# Green_Loop.net
KiCad netlist of a schematic drawn in Altium Designer
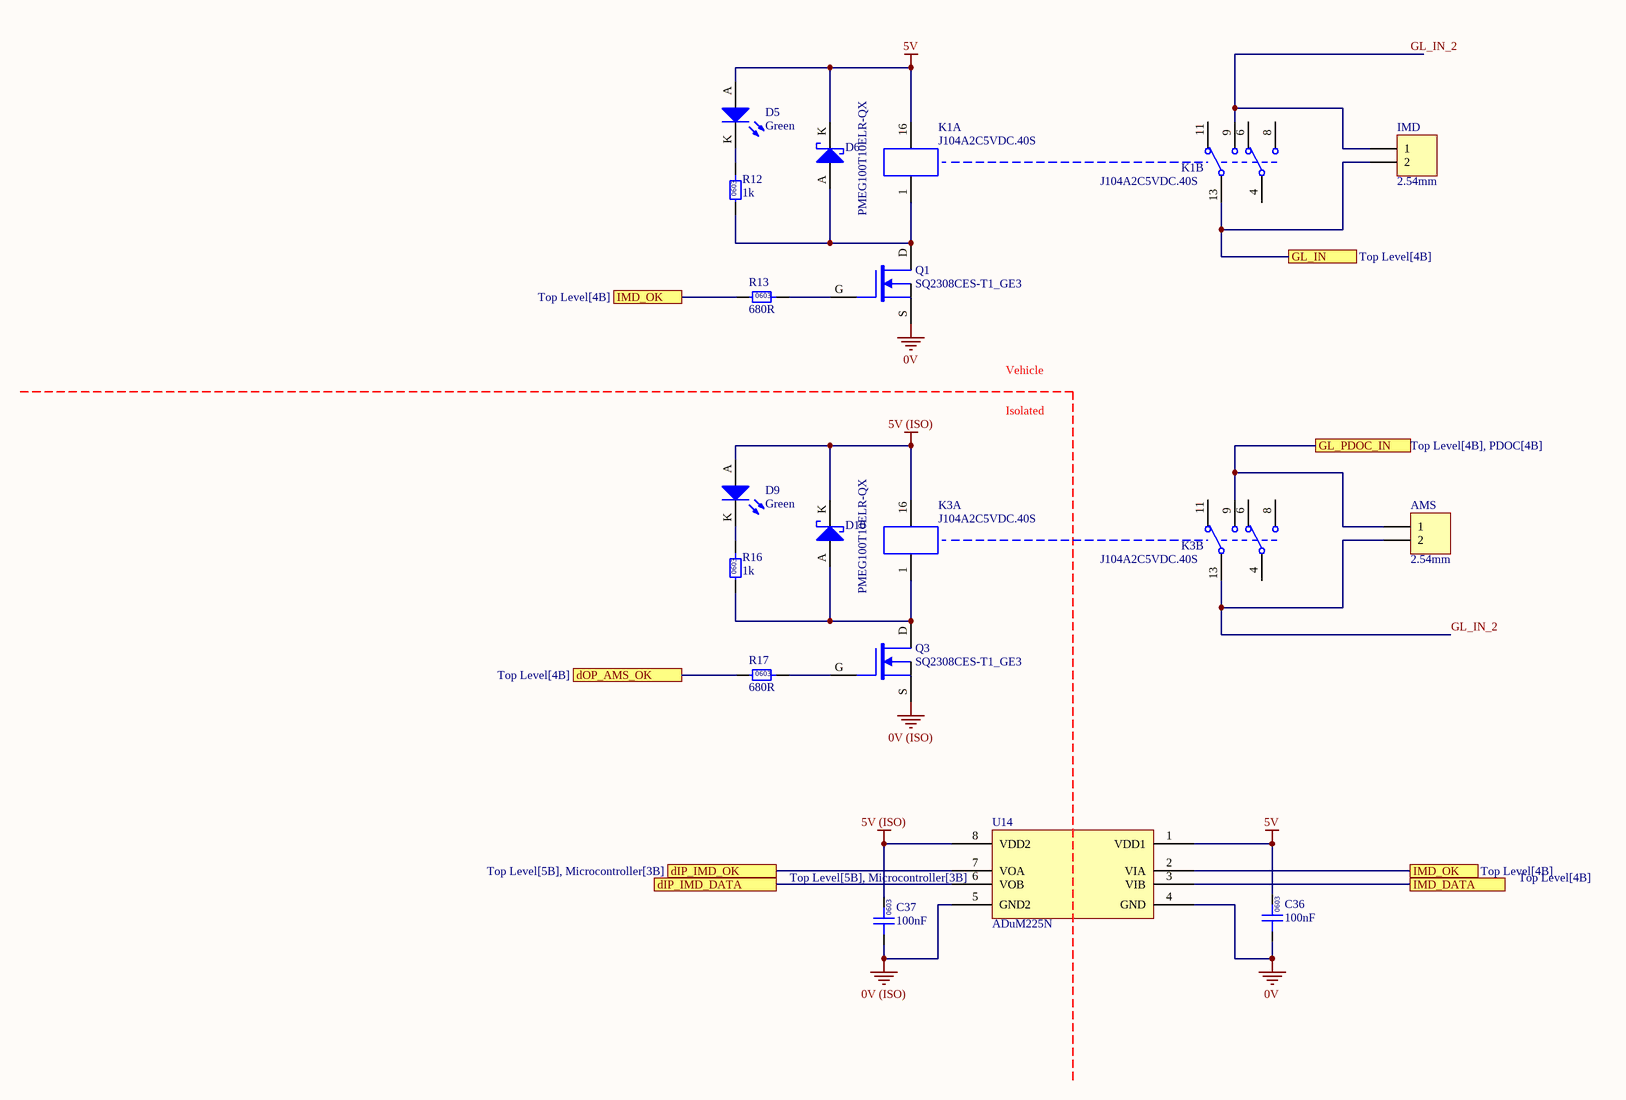
[diagram p0: Green Loop.SchDoc]

(export (version "E")
  (design (tool "Eeschema 10.0.6"))
  (components
    (comp (ref "AMS")
      (value "2.54mm")
      (footprint "TH 2.54mm Header 1x2")
      (fields (field (name "PART NUMBER") "TH 2.54mm Header 1x2") (field (name "CONTACT") "NA"))
      (libsource (lib "ts_standard_connectors") (part "Header 1x2"))
    )
    (comp (ref "C36")
      (value "100nF")
      (footprint "0603")
      (fields
        (field (name "PART NUMBER") "GCM188L81H104KA57D")
        (field (name "MANUFACTURER") "muRata")
        (field (name "TOLERANCE") "±10%")
      )
      (libsource (lib "ts_standard_library") (part "Capacitor 0603"))
    )
    (comp (ref "C37")
      (value "100nF")
      (footprint "0603")
      (fields
        (field (name "PART NUMBER") "GCM188L81H104KA57D")
        (field (name "MANUFACTURER") "muRata")
        (field (name "TOLERANCE") "±10%")
      )
      (libsource (lib "ts_standard_library") (part "Capacitor 0603"))
    )
    (comp (ref "D5")
      (value "Green")
      (footprint "0805 LED")
      (description "Green LED Indication - Discrete 1.75V 0805 (2012 Metric)")
      (fields (field (name "PART NUMBER") "SML-210FTT86") (field (name "MANUFACTURER") "ROHM Semiconductor"))
      (libsource (lib "ts_20-standard-library") (part "LED"))
    )
    (comp (ref "D6")
      (value "PMEG100T10ELR-QX")
      (footprint "NXP SOD123W")
      (fields
        (field (name "MANUFACTURER") "Nexperia USA Inc.")
        (field (name "DIGIKEY PART NUMBER") "1727-PMEG100T10ELR-QXCT-ND")
      )
      (libsource (lib "ts_standard_library") (part "Diode (Schottky)"))
    )
    (comp (ref "D9")
      (value "Green")
      (footprint "0805 LED")
      (description "Green LED Indication - Discrete 1.75V 0805 (2012 Metric)")
      (fields (field (name "PART NUMBER") "SML-210FTT86") (field (name "MANUFACTURER") "ROHM Semiconductor"))
      (libsource (lib "ts_20-standard-library") (part "LED"))
    )
    (comp (ref "D10")
      (value "PMEG100T10ELR-QX")
      (footprint "NXP SOD123W")
      (fields
        (field (name "MANUFACTURER") "Nexperia USA Inc.")
        (field (name "DIGIKEY PART NUMBER") "1727-PMEG100T10ELR-QXCT-ND")
      )
      (libsource (lib "ts_standard_library") (part "Diode (Schottky)"))
    )
    (comp (ref "IMD")
      (value "2.54mm")
      (footprint "TH 2.54mm Header 1x2")
      (fields (field (name "PART NUMBER") "TH 2.54mm Header 1x2") (field (name "CONTACT") "NA"))
      (libsource (lib "ts_standard_connectors") (part "Header 1x2"))
    )
    (comp (ref "K1")
      (value "J104A2C5VDC.40S")
      (footprint "TI 2-DIL")
      (description "RELAY GEN PURPOSE DPDT 3A 5V")
      (fields
        (field (name "MANUFACTURER") "CIT Relay and Switch")
        (field (name "DIGIKEY PART NUMBER") "2449-J104A2C5VDC.40S-ND")
      )
      (libsource (lib "") (part "J104A2C5VDC.40S_1"))
    )
    (comp (ref "K3")
      (value "J104A2C5VDC.40S")
      (footprint "TI 2-DIL")
      (description "RELAY GEN PURPOSE DPDT 3A 5V")
      (fields
        (field (name "MANUFACTURER") "CIT Relay and Switch")
        (field (name "DIGIKEY PART NUMBER") "2449-J104A2C5VDC.40S-ND")
      )
      (libsource (lib "ts_standard_library") (part "J104A2C5VDC.40S"))
    )
    (comp (ref "Q1")
      (value "SQ2308CES-T1_GE3")
      (footprint "VSHY SOT-23-3")
      (description "MOSFET N-CH 60V 2.3A SOT23")
      (fields
        (field (name "MANUFACTURER") "Vishay Siliconix")
        (field (name "DIGIKEY PART NUMBER") "SQ2308CES-T1_GE3CT-ND")
        (field (name "PUBLISHER") "Altium Limited")
      )
      (libsource (lib "ts_standard_library") (part "MOSFET-N"))
    )
    (comp (ref "Q3")
      (value "SQ2308CES-T1_GE3")
      (footprint "VSHY SOT-23-3")
      (description "MOSFET N-CH 60V 2.3A SOT23")
      (fields
        (field (name "MANUFACTURER") "Vishay Siliconix")
        (field (name "DIGIKEY PART NUMBER") "SQ2308CES-T1_GE3CT-ND")
        (field (name "PUBLISHER") "Altium Limited")
      )
      (libsource (lib "ts_standard_library") (part "MOSFET-N"))
    )
    (comp (ref "R12")
      (value "1k")
      (footprint "0603")
      (fields
        (field (name "PART NUMBER") "RC0603FR-071KL")
        (field (name "MANUFACTURER") "YAGEO")
        (field (name "TOLERANCE") "0.01")
      )
      (libsource (lib "ts_standard_library") (part "Resistor 0603"))
    )
    (comp (ref "R13")
      (value "680R")
      (footprint "0603")
      (fields
        (field (name "PART NUMBER") "RC0603JR-13680RL")
        (field (name "MANUFACTURER") "YAGEO")
        (field (name "TOLERANCE") "0.01")
      )
      (libsource (lib "ts_standard_library") (part "Resistor 0603"))
    )
    (comp (ref "R16")
      (value "1k")
      (footprint "0603")
      (fields
        (field (name "PART NUMBER") "RC0603FR-071KL")
        (field (name "MANUFACTURER") "YAGEO")
        (field (name "TOLERANCE") "0.01")
      )
      (libsource (lib "ts_standard_library") (part "Resistor 0603"))
    )
    (comp (ref "R17")
      (value "680R")
      (footprint "0603")
      (fields
        (field (name "PART NUMBER") "RC0603JR-13680RL")
        (field (name "MANUFACTURER") "YAGEO")
        (field (name "TOLERANCE") "0.01")
      )
      (libsource (lib "ts_standard_library") (part "Resistor 0603"))
    )
    (comp (ref "U14")
      (value "ADuM225N")
      (footprint "AD-SOIC-8W")
      (description "DIGITAL ISOLATOR, DUAL CHANNEL")
      (fields (field (name "MANUFACTURER") "Analogue Devices"))
      (libsource (lib "ts_standard_library") (part "ADuM225N"))
    )
  )
  (nets
    (net (code "1") (name "/GL_IN") (class "Default")
      (node (ref "IMD") (pin "2") (pinfunction "2_2") (pintype "passive"))
      (node (ref "K1") (pin "13") (pinfunction "13_13") (pintype "passive"))
    )
    (net (code "2") (name "/GL_IN_2") (class "Default")
      (node (ref "AMS") (pin "2") (pinfunction "2_2") (pintype "passive"))
      (node (ref "IMD") (pin "1") (pinfunction "1_1") (pintype "passive"))
      (node (ref "K1") (pin "9") (pinfunction "9_9") (pintype "passive"))
      (node (ref "K3") (pin "13") (pinfunction "13_13") (pintype "passive"))
    )
    (net (code "3") (name "/GL_PDOC_IN") (class "Default")
      (node (ref "AMS") (pin "1") (pinfunction "1_1") (pintype "passive"))
      (node (ref "K3") (pin "9") (pinfunction "9_9") (pintype "passive"))
    )
    (net (code "4") (name "/IMD_DATA") (class "Default")
      (node (ref "U14") (pin "3") (pinfunction "VIB_3") (pintype "passive"))
    )
    (net (code "5") (name "/IMD_OK") (class "Default")
      (node (ref "R13") (pin "1") (pinfunction "1_1") (pintype "passive"))
      (node (ref "U14") (pin "2") (pinfunction "VIA_2") (pintype "passive"))
    )
    (net (code "6") (name "/dIP_IMD_DATA") (class "Default")
      (node (ref "U14") (pin "6") (pinfunction "VOB_6") (pintype "passive"))
    )
    (net (code "7") (name "/dIP_IMD_OK") (class "Default")
      (node (ref "U14") (pin "7") (pinfunction "VOA_7") (pintype "passive"))
    )
    (net (code "8") (name "/dOP_AMS_OK") (class "Default")
      (node (ref "R17") (pin "1") (pinfunction "1_1") (pintype "passive"))
    )
    (net (code "9") (name "0V") (class "Default")
      (node (ref "C36") (pin "1") (pinfunction "1_1") (pintype "passive"))
      (node (ref "Q1") (pin "S") (pinfunction "S_S") (pintype "passive"))
      (node (ref "U14") (pin "4") (pinfunction "GND_4") (pintype "passive"))
    )
    (net (code "10") (name "0V (ISO)") (class "Default")
      (node (ref "C37") (pin "1") (pinfunction "1_1") (pintype "passive"))
      (node (ref "Q3") (pin "S") (pinfunction "S_S") (pintype "passive"))
      (node (ref "U14") (pin "5") (pinfunction "GND2_5") (pintype "passive"))
    )
    (net (code "11") (name "5V") (class "Default")
      (node (ref "C36") (pin "2") (pinfunction "2_2") (pintype "passive"))
      (node (ref "D5") (pin "A") (pinfunction "A_A") (pintype "passive"))
      (node (ref "D6") (pin "K") (pinfunction "K_K") (pintype "passive"))
      (node (ref "K1") (pin "16") (pinfunction "16_16") (pintype "passive"))
      (node (ref "U14") (pin "1") (pinfunction "VDD1_1") (pintype "passive"))
    )
    (net (code "12") (name "5V (ISO)") (class "Default")
      (node (ref "C37") (pin "2") (pinfunction "2_2") (pintype "passive"))
      (node (ref "D10") (pin "K") (pinfunction "K_K") (pintype "passive"))
      (node (ref "D9") (pin "A") (pinfunction "A_A") (pintype "passive"))
      (node (ref "K3") (pin "16") (pinfunction "16_16") (pintype "passive"))
      (node (ref "U14") (pin "8") (pinfunction "VDD2_8") (pintype "passive"))
    )
    (net (code "13") (name "Net-(D5-PadK)") (class "Default")
      (node (ref "D5") (pin "K") (pinfunction "K_K") (pintype "passive"))
      (node (ref "R12") (pin "2") (pinfunction "2_2") (pintype "passive"))
    )
    (net (code "14") (name "Net-(D6-PadA)") (class "Default")
      (node (ref "D6") (pin "A") (pinfunction "A_A") (pintype "passive"))
      (node (ref "K1") (pin "1") (pinfunction "1_1") (pintype "passive"))
      (node (ref "Q1") (pin "D") (pinfunction "D_D") (pintype "passive"))
      (node (ref "R12") (pin "1") (pinfunction "1_1") (pintype "passive"))
    )
    (net (code "15") (name "Net-(D9-PadK)") (class "Default")
      (node (ref "D9") (pin "K") (pinfunction "K_K") (pintype "passive"))
      (node (ref "R16") (pin "2") (pinfunction "2_2") (pintype "passive"))
    )
    (net (code "16") (name "Net-(D10-PadA)") (class "Default")
      (node (ref "D10") (pin "A") (pinfunction "A_A") (pintype "passive"))
      (node (ref "K3") (pin "1") (pinfunction "1_1") (pintype "passive"))
      (node (ref "Q3") (pin "D") (pinfunction "D_D") (pintype "passive"))
      (node (ref "R16") (pin "1") (pinfunction "1_1") (pintype "passive"))
    )
    (net (code "17") (name "Net-(Q1-PadG)") (class "Default")
      (node (ref "Q1") (pin "G") (pinfunction "G_G") (pintype "passive"))
      (node (ref "R13") (pin "2") (pinfunction "2_2") (pintype "passive"))
    )
    (net (code "18") (name "Net-(Q3-PadG)") (class "Default")
      (node (ref "Q3") (pin "G") (pinfunction "G_G") (pintype "passive"))
      (node (ref "R17") (pin "2") (pinfunction "2_2") (pintype "passive"))
    )
    (net (code "19") (name "unconnected-(K1-Pad4)") (class "Default")
      (node (ref "K1") (pin "4") (pinfunction "4_4") (pintype "passive"))
    )
    (net (code "20") (name "unconnected-(K1-Pad6)") (class "Default")
      (node (ref "K1") (pin "6") (pinfunction "6_6") (pintype "passive"))
    )
    (net (code "21") (name "unconnected-(K1-Pad8)") (class "Default")
      (node (ref "K1") (pin "8") (pinfunction "8_8") (pintype "passive"))
    )
    (net (code "22") (name "unconnected-(K1-Pad11)") (class "Default")
      (node (ref "K1") (pin "11") (pinfunction "11_11") (pintype "passive"))
    )
    (net (code "23") (name "unconnected-(K3-Pad4)") (class "Default")
      (node (ref "K3") (pin "4") (pinfunction "4_4") (pintype "passive"))
    )
    (net (code "24") (name "unconnected-(K3-Pad6)") (class "Default")
      (node (ref "K3") (pin "6") (pinfunction "6_6") (pintype "passive"))
    )
    (net (code "25") (name "unconnected-(K3-Pad8)") (class "Default")
      (node (ref "K3") (pin "8") (pinfunction "8_8") (pintype "passive"))
    )
    (net (code "26") (name "unconnected-(K3-Pad11)") (class "Default")
      (node (ref "K3") (pin "11") (pinfunction "11_11") (pintype "passive"))
    )
  )
)
